# IO.net
KiCad netlist of a schematic drawn in Altium Designer
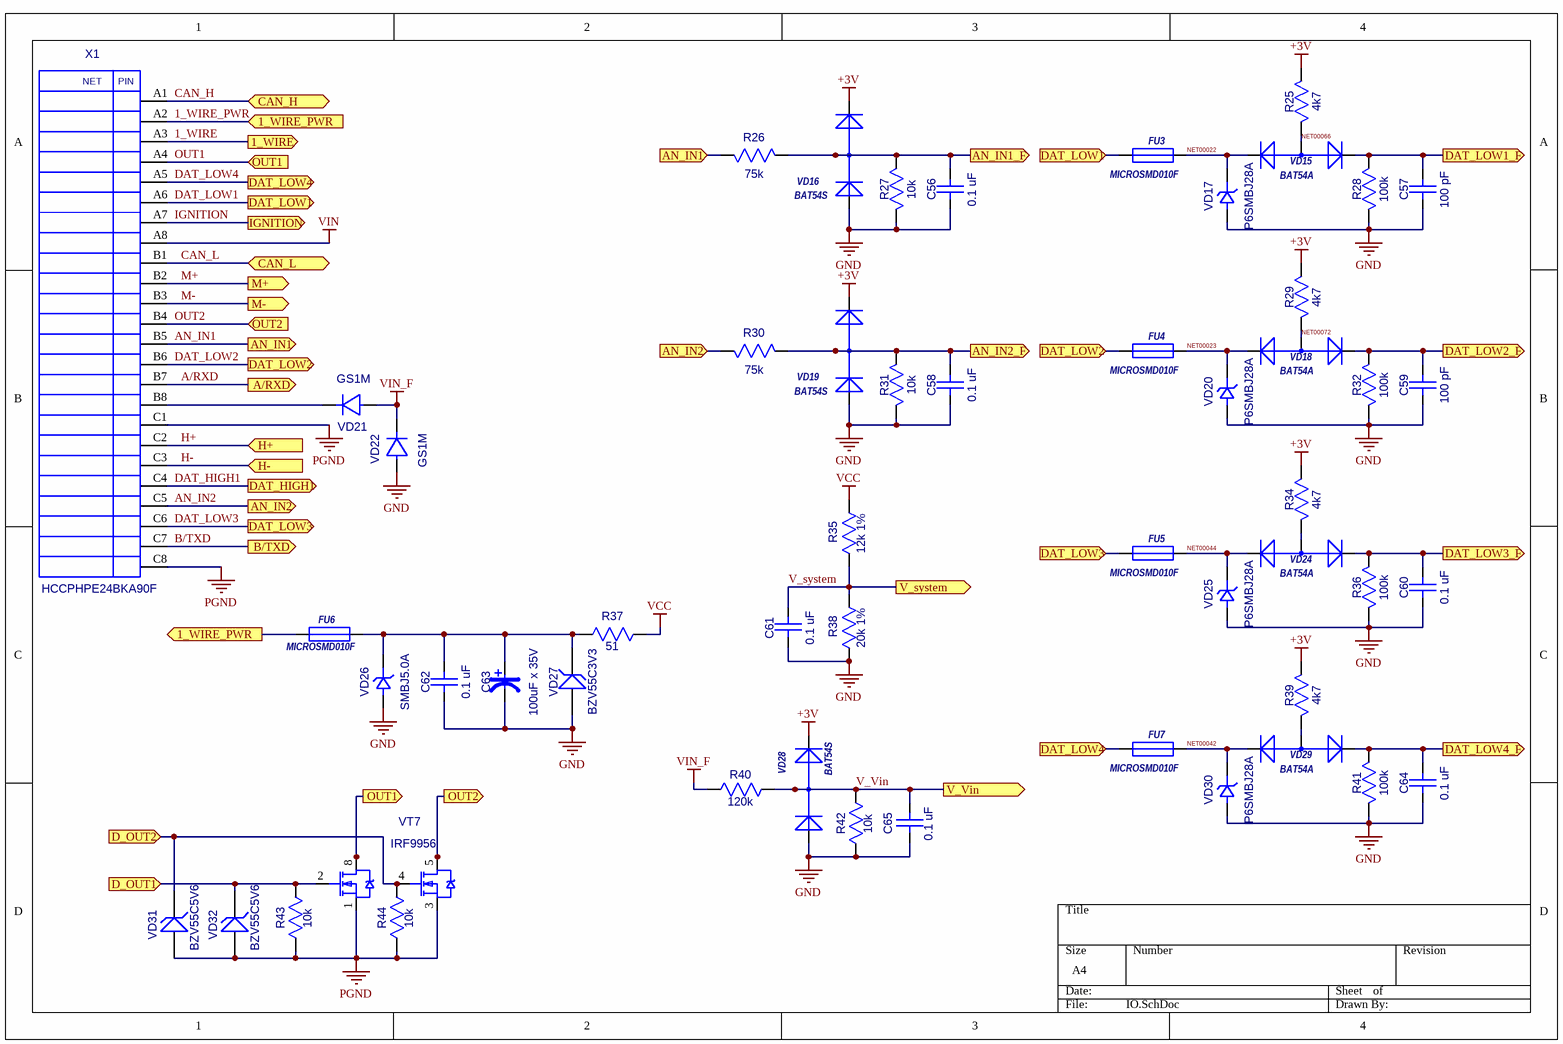
[diagram p0: IO.SchDoc]

(export (version "E")
  (design (tool "Eeschema 10.0.6"))
  (components
    (comp (ref "C56")
      (value "0.1 uF")
      (footprint "CC0603-3M")
      (description "CC0603")
      (libsource (lib "*") (part "CC0603"))
    )
    (comp (ref "C57")
      (value "100 pF")
      (footprint "CC0603-3M")
      (description "CC0603")
      (libsource (lib "*") (part "CC0603"))
    )
    (comp (ref "C58")
      (value "0.1 uF")
      (footprint "CC0603-3M")
      (description "CC0603")
      (libsource (lib "*") (part "CC0603"))
    )
    (comp (ref "C59")
      (value "100 pF")
      (footprint "CC0603-3M")
      (description "CC0603")
      (libsource (lib "*") (part "CC0603"))
    )
    (comp (ref "C60")
      (value "0.1 uF")
      (footprint "CC0603-3M")
      (description "CC0603")
      (libsource (lib "*") (part "CC0603"))
    )
    (comp (ref "C61")
      (value "0.1 uF")
      (footprint "CC0603-3M")
      (description "CC0603")
      (libsource (lib "gprs_modem") (part "CC0603"))
    )
    (comp (ref "C62")
      (value "0.1 uF")
      (footprint "CC0603-3M")
      (description "CC0603")
      (libsource (lib "*") (part "CC0603"))
    )
    (comp (ref "C63")
      (value "100uF x 35V")
      (footprint "CC20X2.54")
      (description "CAP0.25")
      (libsource (lib "*") (part "CAP0.25"))
    )
    (comp (ref "C64")
      (value "0.1 uF")
      (footprint "CC0603-3M")
      (description "CC0603")
      (libsource (lib "*") (part "CC0603"))
    )
    (comp (ref "C65")
      (value "0.1 uF")
      (footprint "CC0603-3M")
      (description "CC0603")
      (libsource (lib "gprs_modem") (part "CC0603"))
    )
    (comp (ref "FU3")
      (value "MICROSMD010F")
      (footprint "RC1210")
      (description "MICROSMD")
      (libsource (lib "*") (part "MICROSMD"))
    )
    (comp (ref "FU4")
      (value "MICROSMD010F")
      (footprint "RC1210")
      (description "MICROSMD")
      (libsource (lib "*") (part "MICROSMD"))
    )
    (comp (ref "FU5")
      (value "MICROSMD010F")
      (footprint "RC1210")
      (description "MICROSMD")
      (libsource (lib "*") (part "MICROSMD"))
    )
    (comp (ref "FU6")
      (value "MICROSMD010F")
      (footprint "RC1210")
      (description "MICROSMD")
      (libsource (lib "*") (part "MICROSMD"))
    )
    (comp (ref "FU7")
      (value "MICROSMD010F")
      (footprint "RC1210")
      (description "MICROSMD")
      (libsource (lib "*") (part "MICROSMD"))
    )
    (comp (ref "R25")
      (value "4k7")
      (footprint "RC0603-3M")
      (description "RC0603")
      (libsource (lib "*") (part "RC0603"))
    )
    (comp (ref "R26")
      (value "75k")
      (footprint "RC0603-3M")
      (description "RC0603")
      (libsource (lib "*") (part "RC0603"))
    )
    (comp (ref "R27")
      (value "10k")
      (footprint "RC0603-3M")
      (description "RC0603")
      (libsource (lib "*") (part "RC0603"))
    )
    (comp (ref "R28")
      (value "100k")
      (footprint "RC0603-3M")
      (description "RC0603")
      (libsource (lib "*") (part "RC0603"))
    )
    (comp (ref "R29")
      (value "4k7")
      (footprint "RC0603-3M")
      (description "RC0603")
      (libsource (lib "*") (part "RC0603"))
    )
    (comp (ref "R30")
      (value "75k")
      (footprint "RC0603-3M")
      (description "RC0603")
      (libsource (lib "*") (part "RC0603"))
    )
    (comp (ref "R31")
      (value "10k")
      (footprint "RC0603-3M")
      (description "RC0603")
      (libsource (lib "*") (part "RC0603"))
    )
    (comp (ref "R32")
      (value "100k")
      (footprint "RC0603-3M")
      (description "RC0603")
      (libsource (lib "*") (part "RC0603"))
    )
    (comp (ref "R34")
      (value "4k7")
      (footprint "RC0603-3M")
      (description "RC0603")
      (libsource (lib "*") (part "RC0603"))
    )
    (comp (ref "R35")
      (value "12k 1%")
      (footprint "RC0603-3M")
      (description "RC0603")
      (libsource (lib "*") (part "RC0603"))
    )
    (comp (ref "R36")
      (value "100k")
      (footprint "RC0603-3M")
      (description "RC0603")
      (libsource (lib "*") (part "RC0603"))
    )
    (comp (ref "R37")
      (value "51")
      (footprint "RC1206-2M")
      (description "RC1206")
      (libsource (lib "*") (part "RC1206"))
    )
    (comp (ref "R38")
      (value "20k 1%")
      (footprint "RC0603-3M")
      (description "RC0603")
      (libsource (lib "*") (part "RC0603"))
    )
    (comp (ref "R39")
      (value "4k7")
      (footprint "RC0603-3M")
      (description "RC0603")
      (libsource (lib "*") (part "RC0603"))
    )
    (comp (ref "R40")
      (value "120k")
      (footprint "RC0603-3M")
      (description "RC0603")
      (libsource (lib "*") (part "RC0603"))
    )
    (comp (ref "R41")
      (value "100k")
      (footprint "RC0603-3M")
      (description "RC0603")
      (libsource (lib "*") (part "RC0603"))
    )
    (comp (ref "R42")
      (value "10k")
      (footprint "RC0603-3M")
      (description "RC0603")
      (libsource (lib "*") (part "RC0603"))
    )
    (comp (ref "R43")
      (value "10k")
      (footprint "RC0603-3M")
      (description "RC0603")
      (libsource (lib "*") (part "RC0603"))
    )
    (comp (ref "R44")
      (value "10k")
      (footprint "RC0603-3M")
      (description "RC0603")
      (libsource (lib "*") (part "RC0603"))
    )
    (comp (ref "VD15")
      (value "BAT54A")
      (footprint "SOT-23(123)")
      (description "1.0 Ampere General Purpose Rectifier")
      (libsource (lib "*") (part "BAT54A"))
    )
    (comp (ref "VD16")
      (value "BAT54S")
      (footprint "SOT-23(GSD)")
      (description "1.0 Ampere General Purpose Rectifier")
      (libsource (lib "*") (part "BAT54S"))
    )
    (comp (ref "VD17")
      (value "P6SMBJ28A")
      (footprint "SMB")
      (description "SMBJ")
      (libsource (lib "gprs_modem") (part "SMBJ"))
    )
    (comp (ref "VD18")
      (value "BAT54A")
      (footprint "SOT-23(123)")
      (description "1.0 Ampere General Purpose Rectifier")
      (libsource (lib "*") (part "BAT54A"))
    )
    (comp (ref "VD19")
      (value "BAT54S")
      (footprint "SOT-23(GSD)")
      (description "1.0 Ampere General Purpose Rectifier")
      (libsource (lib "*") (part "BAT54S"))
    )
    (comp (ref "VD20")
      (value "P6SMBJ28A")
      (footprint "SMB")
      (description "SMBJ")
      (libsource (lib "gprs_modem") (part "SMBJ"))
    )
    (comp (ref "VD21") (value "GS1M") (footprint "SMA") (libsource (lib "gprs_modem") (part "GS1M")))
    (comp (ref "VD22") (value "GS1M") (footprint "SMA") (libsource (lib "gprs_modem") (part "GS1M")))
    (comp (ref "VD24")
      (value "BAT54A")
      (footprint "SOT-23(123)")
      (description "1.0 Ampere General Purpose Rectifier")
      (libsource (lib "*") (part "BAT54A"))
    )
    (comp (ref "VD25")
      (value "P6SMBJ28A")
      (footprint "SMB")
      (description "SMBJ")
      (libsource (lib "gprs_modem") (part "SMBJ"))
    )
    (comp (ref "VD26")
      (value "SMBJ5.0A")
      (footprint "SMB")
      (description "SMBJ")
      (libsource (lib "*") (part "SMBJ"))
    )
    (comp (ref "VD27")
      (value "BZV55C3V3")
      (footprint "SOD-80")
      (description "Zener Voltage Regulator Diode")
      (libsource (lib "*") (part "BZV55C12"))
    )
    (comp (ref "VD28")
      (value "BAT54S")
      (footprint "SOT-23(GSD)")
      (description "1.0 Ampere General Purpose Rectifier")
      (libsource (lib "gprs_modem") (part "BAT54S"))
    )
    (comp (ref "VD29")
      (value "BAT54A")
      (footprint "SOT-23(123)")
      (description "1.0 Ampere General Purpose Rectifier")
      (libsource (lib "*") (part "BAT54A"))
    )
    (comp (ref "VD30")
      (value "P6SMBJ28A")
      (footprint "SMB")
      (description "SMBJ")
      (libsource (lib "gprs_modem") (part "SMBJ"))
    )
    (comp (ref "VD31")
      (value "BZV55C5V6")
      (footprint "SOD-80")
      (description "Zener Voltage Regulator Diode")
      (libsource (lib "*") (part "BZV55C3V0"))
    )
    (comp (ref "VD32")
      (value "BZV55C5V6")
      (footprint "SOD-80")
      (description "Zener Voltage Regulator Diode")
      (libsource (lib "*") (part "BZV55C3V0"))
    )
    (comp (ref "VT7")
      (value "IRF9956")
      (footprint "SO-8")
      (description "HEXFET Power MOSFET")
      (libsource (lib "*") (part "IRF9956"))
    )
    (comp (ref "X1")
      (value "HCCPHPE24BKA90F")
      (footprint "HCCPHPE24BKA90F_HCCPHPE24BKA90F(Primary)")
      (libsource (lib "gprs_modem") (part "HCCPHPE24BKA90F"))
    )
  )
  (nets
    (net (code "1") (name "+3V") (class "Default")
      (node (ref "R25") (pin "1") (pinfunction "A_1") (pintype "passive"))
      (node (ref "R29") (pin "1") (pinfunction "A_1") (pintype "passive"))
      (node (ref "R34") (pin "1") (pinfunction "A_1") (pintype "passive"))
      (node (ref "R39") (pin "1") (pinfunction "A_1") (pintype "passive"))
      (node (ref "VD16") (pin "2") (pinfunction "K_2") (pintype "passive"))
      (node (ref "VD19") (pin "2") (pinfunction "K_2") (pintype "passive"))
      (node (ref "VD28") (pin "2") (pinfunction "K_2") (pintype "passive"))
    )
    (net (code "2") (name "/1_WIRE") (class "Default") (node (ref "X1") (pin "A3") (pintype "passive")))
    (net (code "3") (name "/1_WIRE_PWR") (class "Default")
      (node (ref "FU6") (pin "2") (pintype "passive"))
      (node (ref "X1") (pin "A2") (pintype "passive"))
    )
    (net (code "4") (name "/AN_IN1") (class "Default")
      (node (ref "R26") (pin "2") (pinfunction "B_2") (pintype "passive"))
      (node (ref "X1") (pin "B5") (pintype "passive"))
    )
    (net (code "5") (name "/AN_IN1_F") (class "Default")
      (node (ref "C56") (pin "2") (pinfunction "B_2") (pintype "passive"))
      (node (ref "R26") (pin "1") (pinfunction "A_1") (pintype "passive"))
      (node (ref "R27") (pin "1") (pinfunction "A_1") (pintype "passive"))
      (node (ref "VD16") (pin "3") (pinfunction "AK_3") (pintype "passive"))
    )
    (net (code "6") (name "/AN_IN2") (class "Default")
      (node (ref "R30") (pin "2") (pinfunction "B_2") (pintype "passive"))
      (node (ref "X1") (pin "C5") (pintype "passive"))
    )
    (net (code "7") (name "/AN_IN2_F") (class "Default")
      (node (ref "C58") (pin "2") (pinfunction "B_2") (pintype "passive"))
      (node (ref "R30") (pin "1") (pinfunction "A_1") (pintype "passive"))
      (node (ref "R31") (pin "1") (pinfunction "A_1") (pintype "passive"))
      (node (ref "VD19") (pin "3") (pinfunction "AK_3") (pintype "passive"))
    )
    (net (code "8") (name "/A{slash}RXD") (class "Default") (node (ref "X1") (pin "B7") (pintype "passive")))
    (net (code "9") (name "/B{slash}TXD") (class "Default") (node (ref "X1") (pin "C7") (pintype "passive")))
    (net (code "10") (name "/CAN_H") (class "Default") (node (ref "X1") (pin "A1") (pintype "passive")))
    (net (code "11") (name "/CAN_L") (class "Default") (node (ref "X1") (pin "B1") (pintype "passive")))
    (net (code "12") (name "/DAT_HIGH1") (class "Default") (node (ref "X1") (pin "C4") (pintype "passive")))
    (net (code "13") (name "/DAT_LOW1") (class "Default")
      (node (ref "FU3") (pin "2") (pintype "passive"))
      (node (ref "X1") (pin "A6") (pintype "passive"))
    )
    (net (code "14") (name "/DAT_LOW1_F") (class "Default")
      (node (ref "C57") (pin "2") (pinfunction "B_2") (pintype "passive"))
      (node (ref "R28") (pin "1") (pinfunction "A_1") (pintype "passive"))
      (node (ref "VD15") (pin "2") (pinfunction "K_2") (pintype "passive"))
    )
    (net (code "15") (name "/DAT_LOW2") (class "Default")
      (node (ref "FU4") (pin "2") (pintype "passive"))
      (node (ref "X1") (pin "B6") (pintype "passive"))
    )
    (net (code "16") (name "/DAT_LOW2_F") (class "Default")
      (node (ref "C59") (pin "2") (pinfunction "B_2") (pintype "passive"))
      (node (ref "R32") (pin "1") (pinfunction "A_1") (pintype "passive"))
      (node (ref "VD18") (pin "2") (pinfunction "K_2") (pintype "passive"))
    )
    (net (code "17") (name "/DAT_LOW3") (class "Default")
      (node (ref "FU5") (pin "2") (pintype "passive"))
      (node (ref "X1") (pin "C6") (pintype "passive"))
    )
    (net (code "18") (name "/DAT_LOW3_F") (class "Default")
      (node (ref "C60") (pin "2") (pinfunction "B_2") (pintype "passive"))
      (node (ref "R36") (pin "1") (pinfunction "A_1") (pintype "passive"))
      (node (ref "VD24") (pin "2") (pinfunction "K_2") (pintype "passive"))
    )
    (net (code "19") (name "/DAT_LOW4") (class "Default")
      (node (ref "FU7") (pin "2") (pintype "passive"))
      (node (ref "X1") (pin "A5") (pintype "passive"))
    )
    (net (code "20") (name "/DAT_LOW4_F") (class "Default")
      (node (ref "C64") (pin "2") (pinfunction "B_2") (pintype "passive"))
      (node (ref "R41") (pin "1") (pinfunction "A_1") (pintype "passive"))
      (node (ref "VD29") (pin "2") (pinfunction "K_2") (pintype "passive"))
    )
    (net (code "21") (name "/D_OUT1") (class "Default")
      (node (ref "R43") (pin "1") (pinfunction "A_1") (pintype "passive"))
      (node (ref "VD32") (pin "2") (pintype "passive"))
      (node (ref "VT7") (pin "2") (pinfunction "G_2") (pintype "passive"))
    )
    (net (code "22") (name "/D_OUT2") (class "Default")
      (node (ref "R44") (pin "1") (pinfunction "A_1") (pintype "passive"))
      (node (ref "VD31") (pin "2") (pintype "passive"))
      (node (ref "VT7") (pin "4") (pinfunction "G_4") (pintype "passive"))
    )
    (net (code "23") (name "/H+") (class "Default") (node (ref "X1") (pin "C2") (pintype "passive")))
    (net (code "24") (name "/H-") (class "Default") (node (ref "X1") (pin "C3") (pintype "passive")))
    (net (code "25") (name "/IGNITION") (class "Default") (node (ref "X1") (pin "A7") (pintype "passive")))
    (net (code "26") (name "/M+") (class "Default") (node (ref "X1") (pin "B2") (pintype "passive")))
    (net (code "27") (name "/M-") (class "Default") (node (ref "X1") (pin "B3") (pintype "passive")))
    (net (code "28") (name "/NET00022") (class "Default")
      (node (ref "FU3") (pin "1") (pintype "passive"))
      (node (ref "VD15") (pin "1") (pinfunction "K_1") (pintype "passive"))
      (node (ref "VD17") (pin "2") (pinfunction "K_2") (pintype "passive"))
    )
    (net (code "29") (name "/NET00023") (class "Default")
      (node (ref "FU4") (pin "1") (pintype "passive"))
      (node (ref "VD18") (pin "1") (pinfunction "K_1") (pintype "passive"))
      (node (ref "VD20") (pin "2") (pinfunction "K_2") (pintype "passive"))
    )
    (net (code "30") (name "/NET00042") (class "Default")
      (node (ref "FU7") (pin "1") (pintype "passive"))
      (node (ref "VD29") (pin "1") (pinfunction "K_1") (pintype "passive"))
      (node (ref "VD30") (pin "2") (pinfunction "K_2") (pintype "passive"))
    )
    (net (code "31") (name "/NET00044") (class "Default")
      (node (ref "FU5") (pin "1") (pintype "passive"))
      (node (ref "VD24") (pin "1") (pinfunction "K_1") (pintype "passive"))
      (node (ref "VD25") (pin "2") (pinfunction "K_2") (pintype "passive"))
    )
    (net (code "32") (name "/NET00066") (class "Default")
      (node (ref "R25") (pin "2") (pinfunction "B_2") (pintype "passive"))
      (node (ref "VD15") (pin "3") (pinfunction "A_3") (pintype "passive"))
    )
    (net (code "33") (name "/NET00072") (class "Default")
      (node (ref "R29") (pin "2") (pinfunction "B_2") (pintype "passive"))
      (node (ref "VD18") (pin "3") (pinfunction "A_3") (pintype "passive"))
    )
    (net (code "34") (name "/OUT1") (class "Default")
      (node (ref "VT7") (pin "7") (pinfunction "D_7") (pintype "passive"))
      (node (ref "VT7") (pin "8") (pinfunction "D_8") (pintype "passive"))
      (node (ref "X1") (pin "A4") (pintype "passive"))
    )
    (net (code "35") (name "/OUT2") (class "Default")
      (node (ref "VT7") (pin "5") (pinfunction "D_5") (pintype "passive"))
      (node (ref "VT7") (pin "6") (pinfunction "D_6") (pintype "passive"))
      (node (ref "X1") (pin "B4") (pintype "passive"))
    )
    (net (code "36") (name "/V_Vin") (class "Default")
      (node (ref "C65") (pin "1") (pinfunction "A_1") (pintype "passive"))
      (node (ref "R40") (pin "1") (pinfunction "A_1") (pintype "passive"))
      (node (ref "R42") (pin "1") (pinfunction "A_1") (pintype "passive"))
      (node (ref "VD28") (pin "3") (pinfunction "AK_3") (pintype "passive"))
    )
    (net (code "37") (name "/V_system") (class "Default")
      (node (ref "C61") (pin "1") (pinfunction "A_1") (pintype "passive"))
      (node (ref "R35") (pin "1") (pinfunction "A_1") (pintype "passive"))
      (node (ref "R38") (pin "2") (pinfunction "B_2") (pintype "passive"))
    )
    (net (code "38") (name "GND") (class "Default")
      (node (ref "C56") (pin "1") (pinfunction "A_1") (pintype "passive"))
      (node (ref "C57") (pin "1") (pinfunction "A_1") (pintype "passive"))
      (node (ref "C58") (pin "1") (pinfunction "A_1") (pintype "passive"))
      (node (ref "C59") (pin "1") (pinfunction "A_1") (pintype "passive"))
      (node (ref "C60") (pin "1") (pinfunction "A_1") (pintype "passive"))
      (node (ref "C61") (pin "2") (pinfunction "B_2") (pintype "passive"))
      (node (ref "C62") (pin "1") (pinfunction "A_1") (pintype "passive"))
      (node (ref "C63") (pin "2") (pinfunction "minus_2") (pintype "passive"))
      (node (ref "C64") (pin "1") (pinfunction "A_1") (pintype "passive"))
      (node (ref "C65") (pin "2") (pinfunction "B_2") (pintype "passive"))
      (node (ref "R27") (pin "2") (pinfunction "B_2") (pintype "passive"))
      (node (ref "R28") (pin "2") (pinfunction "B_2") (pintype "passive"))
      (node (ref "R31") (pin "2") (pinfunction "B_2") (pintype "passive"))
      (node (ref "R32") (pin "2") (pinfunction "B_2") (pintype "passive"))
      (node (ref "R36") (pin "2") (pinfunction "B_2") (pintype "passive"))
      (node (ref "R38") (pin "1") (pinfunction "A_1") (pintype "passive"))
      (node (ref "R41") (pin "2") (pinfunction "B_2") (pintype "passive"))
      (node (ref "R42") (pin "2") (pinfunction "B_2") (pintype "passive"))
      (node (ref "VD16") (pin "1") (pinfunction "A_1") (pintype "passive"))
      (node (ref "VD17") (pin "1") (pinfunction "A_1") (pintype "passive"))
      (node (ref "VD19") (pin "1") (pinfunction "A_1") (pintype "passive"))
      (node (ref "VD20") (pin "1") (pinfunction "A_1") (pintype "passive"))
      (node (ref "VD22") (pin "1") (pinfunction "A_1") (pintype "passive"))
      (node (ref "VD25") (pin "1") (pinfunction "A_1") (pintype "passive"))
      (node (ref "VD26") (pin "1") (pinfunction "A_1") (pintype "passive"))
      (node (ref "VD27") (pin "1") (pinfunction "A_1") (pintype "passive"))
      (node (ref "VD28") (pin "1") (pinfunction "A_1") (pintype "passive"))
      (node (ref "VD30") (pin "1") (pinfunction "A_1") (pintype "passive"))
    )
    (net (code "39") (name "Net-(C62-B)") (class "Default")
      (node (ref "C62") (pin "2") (pinfunction "B_2") (pintype "passive"))
      (node (ref "C63") (pin "1") (pinfunction "plus_1") (pintype "passive"))
      (node (ref "FU6") (pin "1") (pintype "passive"))
      (node (ref "R37") (pin "1") (pinfunction "A_1") (pintype "passive"))
      (node (ref "VD26") (pin "2") (pinfunction "K_2") (pintype "passive"))
      (node (ref "VD27") (pin "2") (pintype "passive"))
    )
    (net (code "40") (name "Net-(R34-B)") (class "Default")
      (node (ref "R34") (pin "2") (pinfunction "B_2") (pintype "passive"))
      (node (ref "VD24") (pin "3") (pinfunction "A_3") (pintype "passive"))
    )
    (net (code "41") (name "Net-(R39-B)") (class "Default")
      (node (ref "R39") (pin "2") (pinfunction "B_2") (pintype "passive"))
      (node (ref "VD29") (pin "3") (pinfunction "A_3") (pintype "passive"))
    )
    (net (code "42") (name "Net-(VD21-K)") (class "Default")
      (node (ref "VD21") (pin "2") (pinfunction "K_2") (pintype "passive"))
      (node (ref "X1") (pin "B8") (pintype "passive"))
    )
    (net (code "43") (name "PGND") (class "Default")
      (node (ref "R43") (pin "2") (pinfunction "B_2") (pintype "passive"))
      (node (ref "R44") (pin "2") (pinfunction "B_2") (pintype "passive"))
      (node (ref "VD31") (pin "1") (pinfunction "A_1") (pintype "passive"))
      (node (ref "VD32") (pin "1") (pinfunction "A_1") (pintype "passive"))
      (node (ref "VT7") (pin "1") (pinfunction "S_1") (pintype "passive"))
      (node (ref "VT7") (pin "3") (pinfunction "S_3") (pintype "passive"))
      (node (ref "X1") (pin "C1") (pintype "passive"))
      (node (ref "X1") (pin "C8") (pintype "passive"))
    )
    (net (code "44") (name "VCC") (class "Default")
      (node (ref "R35") (pin "2") (pinfunction "B_2") (pintype "passive"))
      (node (ref "R37") (pin "2") (pinfunction "B_2") (pintype "passive"))
    )
    (net (code "45") (name "VIN") (class "Default") (node (ref "X1") (pin "A8") (pintype "passive")))
    (net (code "46") (name "VIN_F") (class "Default")
      (node (ref "R40") (pin "2") (pinfunction "B_2") (pintype "passive"))
      (node (ref "VD21") (pin "1") (pinfunction "A_1") (pintype "passive"))
      (node (ref "VD22") (pin "2") (pinfunction "K_2") (pintype "passive"))
    )
  )
)
